# RFM69_20USB_20Gateway.net
KiCad netlist of a schematic drawn in EAGLE
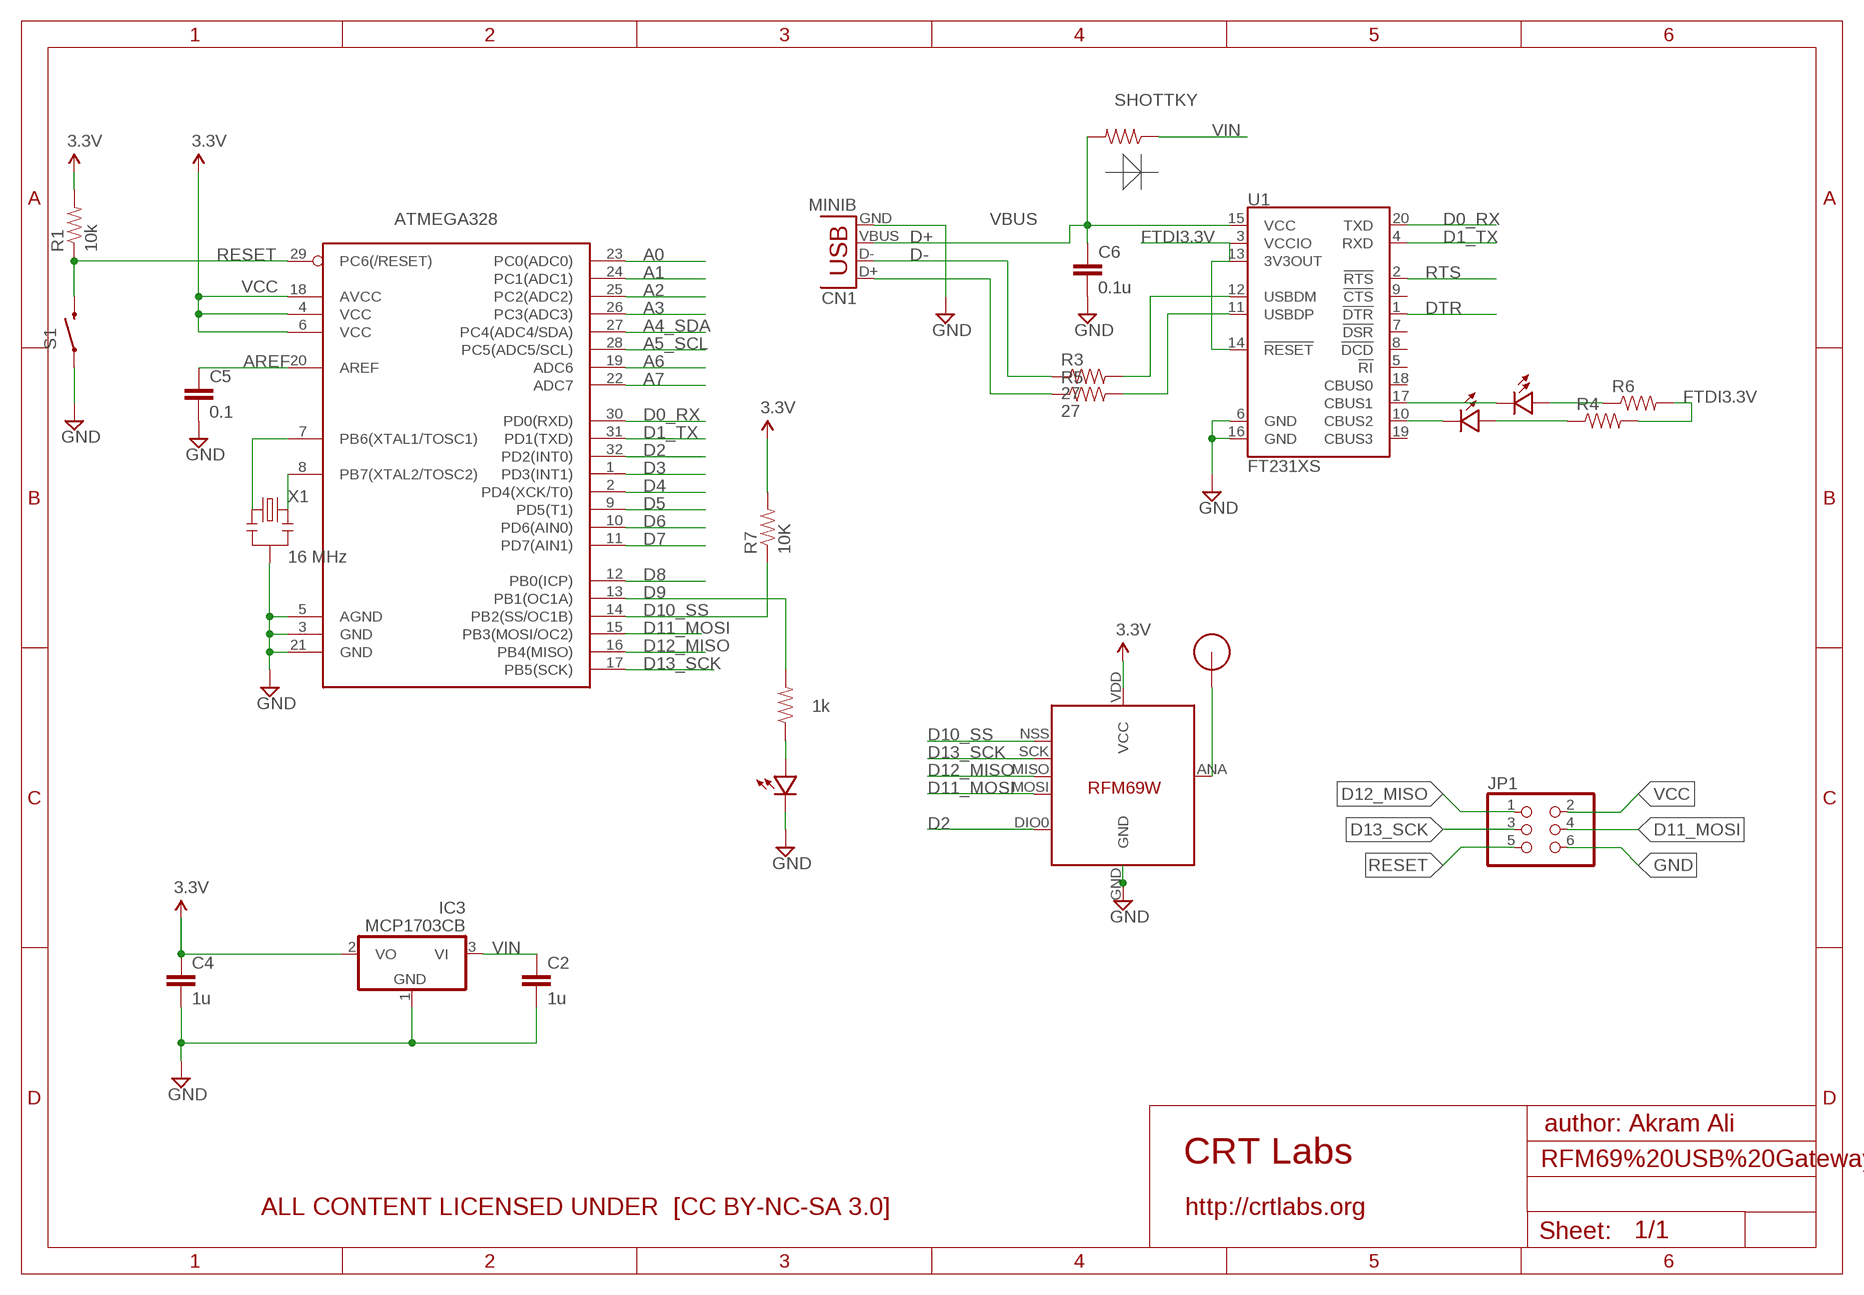
[diagram p0: schematic, sheet 1]

(export (version "E")
  (design (tool "Eeschema 10.0.6"))
  (components
    (comp (ref "ATMEGA328")
      (value "ATMega-328")
      (footprint "eagle-import:TQFP32-08")
      (libsource (lib "eagle-import") (part "ATMEGA168/328TQFP32"))
    )
    (comp (ref "C2")
      (value "1u")
      (footprint "eagle-import:0805")
      (libsource (lib "eagle-import") (part "SparkFun_CAP0805"))
    )
    (comp (ref "C4")
      (value "1u")
      (footprint "eagle-import:0805")
      (libsource (lib "eagle-import") (part "CAP0805"))
    )
    (comp (ref "C5")
      (value "0.1")
      (footprint "eagle-import:0805")
      (libsource (lib "eagle-import") (part "SparkFun_CAP0805"))
    )
    (comp (ref "C6")
      (value "0.1u")
      (footprint "eagle-import:0805")
      (libsource (lib "eagle-import") (part "SparkFun_CAP0805"))
    )
    (comp (ref "CN1")
      (value "MINIB")
      (footprint "eagle-import:USB-A-H")
      (libsource (lib "eagle-import") (part "USB-A-H"))
    )
    (comp (ref "D")
      (value "SHOTTKY")
      (footprint "eagle-import:0805")
      (libsource (lib "eagle-import") (part "RESISTOR0805"))
    )
    (comp (ref "IC3")
      (value "MCP1703CB")
      (footprint "eagle-import:SOT23")
      (libsource (lib "eagle-import") (part "MCP1703CB"))
    )
    (comp (ref "JP1")
      (value "PINHD-2X3")
      (footprint "eagle-import:2X03")
      (libsource (lib "eagle-import") (part "PINHD-2X3"))
    )
    (comp (ref "R1")
      (value "10k")
      (footprint "eagle-import:0805")
      (libsource (lib "eagle-import") (part "RESISTOR0805"))
    )
    (comp (ref "R2")
      (value "1k")
      (footprint "eagle-import:0805")
      (libsource (lib "eagle-import") (part "SparkFun_RESISTOR0805-RES"))
    )
    (comp (ref "R3")
      (value "27")
      (footprint "eagle-import:0805")
      (libsource (lib "eagle-import") (part "SparkFun_RESISTOR0805-RES"))
    )
    (comp (ref "R4")
      (value "RESISTOR0805-RES")
      (footprint "eagle-import:0805")
      (libsource (lib "eagle-import") (part "SparkFun_RESISTOR0805-RES"))
    )
    (comp (ref "R5")
      (value "27")
      (footprint "eagle-import:0805")
      (libsource (lib "eagle-import") (part "SparkFun_RESISTOR0805-RES"))
    )
    (comp (ref "R6")
      (value "RESISTOR0805-RES")
      (footprint "eagle-import:0805")
      (libsource (lib "eagle-import") (part "SparkFun_RESISTOR0805-RES"))
    )
    (comp (ref "R7")
      (value "10K")
      (footprint "eagle-import:0805")
      (libsource (lib "eagle-import") (part "SparkFun_RESISTOR0805-RES"))
    )
    (comp (ref "S1")
      (value "SWITCH-MOMENTARY-2SMD-ALT01")
      (footprint "eagle-import:TACTILE-SWITCH-SMD-ALT01")
      (libsource (lib "eagle-import") (part "SWITCH-MOMENTARY-2SMD-ALT01"))
    )
    (comp (ref "U$1")
      (value "RFM12B_ANTENNA")
      (footprint "eagle-import:RFM12B-ANTENNA")
      (libsource (lib "eagle-import") (part "RFM12B_ANTENNA"))
    )
    (comp (ref "U$2")
      (value "LED0805")
      (footprint "eagle-import:0805-LED")
      (libsource (lib "eagle-import") (part "LED0805"))
    )
    (comp (ref "U$4")
      (value "LED0805")
      (footprint "eagle-import:0805-LED")
      (libsource (lib "eagle-import") (part "LED0805"))
    )
    (comp (ref "U$5")
      (value "RFM69")
      (footprint "eagle-import:RFM69W-MINPADS")
      (libsource (lib "eagle-import") (part "RFM69"))
    )
    (comp (ref "U$7")
      (value "LED0805")
      (footprint "eagle-import:0805-LED")
      (libsource (lib "eagle-import") (part "LED0805"))
    )
    (comp (ref "U1")
      (value "FT231XS")
      (footprint "eagle-import:SSOP20_L")
      (libsource (lib "eagle-import") (part "FT231XS"))
    )
    (comp (ref "X1")
      (value "16 MHz")
      (footprint "eagle-import:RESONATOR-SMD")
      (libsource (lib "eagle-import") (part "RESONATORSMD"))
    )
  )
  (nets
    (net (code "1") (name "/A0") (class "Default")
      (node (ref "ATMEGA328") (pin "23") (pinfunction "PC0(ADC0)_23") (pintype "bidirectional"))
    )
    (net (code "2") (name "/A1") (class "Default")
      (node (ref "ATMEGA328") (pin "24") (pinfunction "PC1(ADC1)_24") (pintype "bidirectional"))
    )
    (net (code "3") (name "/A2") (class "Default")
      (node (ref "ATMEGA328") (pin "25") (pinfunction "PC2(ADC2)_25") (pintype "bidirectional"))
    )
    (net (code "4") (name "/A3") (class "Default")
      (node (ref "ATMEGA328") (pin "26") (pinfunction "PC3(ADC3)_26") (pintype "bidirectional"))
    )
    (net (code "5") (name "/A4_SDA") (class "Default")
      (node (ref "ATMEGA328") (pin "27") (pinfunction "PC4(ADC4/SDA)_27") (pintype "bidirectional"))
    )
    (net (code "6") (name "/A5_SCL") (class "Default")
      (node (ref "ATMEGA328") (pin "28") (pinfunction "PC5(ADC5/SCL)_28") (pintype "bidirectional"))
    )
    (net (code "7") (name "/A6") (class "Default")
      (node (ref "ATMEGA328") (pin "19") (pinfunction "ADC6_19") (pintype "bidirectional"))
    )
    (net (code "8") (name "/A7") (class "Default")
      (node (ref "ATMEGA328") (pin "22") (pinfunction "ADC7_22") (pintype "bidirectional"))
    )
    (net (code "9") (name "/AREF") (class "Default")
      (node (ref "ATMEGA328") (pin "20") (pinfunction "AREF_20") (pintype "bidirectional"))
      (node (ref "C5") (pin "1") (pinfunction "1_1") (pintype "passive"))
    )
    (net (code "10") (name "/D+") (class "Default")
      (node (ref "CN1") (pin "D+") (pinfunction "D+_D+") (pintype "bidirectional"))
      (node (ref "R5") (pin "1") (pinfunction "1_1") (pintype "passive"))
    )
    (net (code "11") (name "/D-") (class "Default")
      (node (ref "CN1") (pin "D-") (pinfunction "D-_D-") (pintype "bidirectional"))
      (node (ref "R3") (pin "1") (pinfunction "1_1") (pintype "passive"))
    )
    (net (code "12") (name "/D0_RX") (class "Default")
      (node (ref "ATMEGA328") (pin "30") (pinfunction "PD0(RXD)_30") (pintype "bidirectional"))
      (node (ref "U1") (pin "20") (pinfunction "TXD_20") (pintype "bidirectional"))
    )
    (net (code "13") (name "/D1_TX") (class "Default")
      (node (ref "ATMEGA328") (pin "31") (pinfunction "PD1(TXD)_31") (pintype "bidirectional"))
      (node (ref "U1") (pin "4") (pinfunction "RXD_4") (pintype "bidirectional"))
    )
    (net (code "14") (name "/D2") (class "Default")
      (node (ref "ATMEGA328") (pin "32") (pinfunction "PD2(INT0)_32") (pintype "bidirectional"))
      (node (ref "U$5") (pin "DIO0") (pinfunction "DIO0_DIO0") (pintype "open_collector"))
    )
    (net (code "15") (name "/D3") (class "Default")
      (node (ref "ATMEGA328") (pin "1") (pinfunction "PD3(INT1)_1") (pintype "bidirectional"))
    )
    (net (code "16") (name "/D4") (class "Default")
      (node (ref "ATMEGA328") (pin "2") (pinfunction "PD4(XCK/T0)_2") (pintype "bidirectional"))
    )
    (net (code "17") (name "/D5") (class "Default")
      (node (ref "ATMEGA328") (pin "9") (pinfunction "PD5(T1)_9") (pintype "bidirectional"))
    )
    (net (code "18") (name "/D6") (class "Default")
      (node (ref "ATMEGA328") (pin "10") (pinfunction "PD6(AIN0)_10") (pintype "bidirectional"))
    )
    (net (code "19") (name "/D7") (class "Default")
      (node (ref "ATMEGA328") (pin "11") (pinfunction "PD7(AIN1)_11") (pintype "bidirectional"))
    )
    (net (code "20") (name "/D8") (class "Default")
      (node (ref "ATMEGA328") (pin "12") (pinfunction "PB0(ICP)_12") (pintype "bidirectional"))
    )
    (net (code "21") (name "/D9") (class "Default")
      (node (ref "ATMEGA328") (pin "13") (pinfunction "PB1(OC1A)_13") (pintype "bidirectional"))
      (node (ref "R2") (pin "2") (pinfunction "2_2") (pintype "passive"))
    )
    (net (code "22") (name "/D10_SS") (class "Default")
      (node (ref "ATMEGA328") (pin "14") (pinfunction "PB2(SS/OC1B)_14") (pintype "bidirectional"))
      (node (ref "R7") (pin "1") (pinfunction "1_1") (pintype "passive"))
      (node (ref "U$5") (pin "NSS") (pinfunction "SEL_NSS") (pintype "input"))
    )
    (net (code "23") (name "/DTR") (class "Default")
      (node (ref "U1") (pin "1") (pinfunction "~{DTR}_1") (pintype "bidirectional"))
    )
    (net (code "24") (name "/FTDI3.3V") (class "Default")
      (node (ref "R4") (pin "2") (pinfunction "2_2") (pintype "passive"))
      (node (ref "R6") (pin "2") (pinfunction "2_2") (pintype "passive"))
      (node (ref "U1") (pin "13") (pinfunction "3V3OUT_13") (pintype "bidirectional"))
      (node (ref "U1") (pin "14") (pinfunction "~{RESET}_14") (pintype "bidirectional"))
      (node (ref "U1") (pin "3") (pinfunction "VCCIO_3") (pintype "bidirectional"))
    )
    (net (code "25") (name "/RTS") (class "Default")
      (node (ref "U1") (pin "2") (pinfunction "~{RTS}_2") (pintype "bidirectional"))
    )
    (net (code "26") (name "/VBUS") (class "Default")
      (node (ref "C6") (pin "1") (pinfunction "1_1") (pintype "passive"))
      (node (ref "CN1") (pin "VBUS") (pinfunction "VBUS_VBUS") (pintype "bidirectional"))
      (node (ref "D") (pin "2") (pinfunction "2_2") (pintype "passive"))
      (node (ref "U1") (pin "15") (pinfunction "VCC_15") (pintype "bidirectional"))
    )
    (net (code "27") (name "/VIN") (class "Default")
      (node (ref "C2") (pin "1") (pinfunction "1_1") (pintype "passive"))
      (node (ref "D") (pin "1") (pinfunction "1_1") (pintype "passive"))
      (node (ref "IC3") (pin "3") (pinfunction "VI_3") (pintype "input"))
    )
    (net (code "28") (name "D11_MOSI") (class "Default")
      (node (ref "ATMEGA328") (pin "15") (pinfunction "PB3(MOSI/OC2)_15") (pintype "bidirectional"))
      (node (ref "JP1") (pin "4") (pinfunction "4_4") (pintype "passive"))
      (node (ref "U$5") (pin "MOSI") (pinfunction "MOSI_MOSI") (pintype "output"))
    )
    (net (code "29") (name "D12_MISO") (class "Default")
      (node (ref "ATMEGA328") (pin "16") (pinfunction "PB4(MISO)_16") (pintype "bidirectional"))
      (node (ref "JP1") (pin "1") (pinfunction "1_1") (pintype "passive"))
      (node (ref "U$5") (pin "MISO") (pinfunction "MISO_MISO") (pintype "input"))
    )
    (net (code "30") (name "D13_SCK") (class "Default")
      (node (ref "ATMEGA328") (pin "17") (pinfunction "PB5(SCK)_17") (pintype "bidirectional"))
      (node (ref "JP1") (pin "3") (pinfunction "3_3") (pintype "passive"))
      (node (ref "U$5") (pin "SCK") (pinfunction "SCK_SCK") (pintype "input"))
    )
    (net (code "31") (name "GND") (class "Default")
      (node (ref "ATMEGA328") (pin "21") (pinfunction "GND_21") (pintype "bidirectional"))
      (node (ref "ATMEGA328") (pin "3") (pinfunction "GND_3") (pintype "bidirectional"))
      (node (ref "ATMEGA328") (pin "5") (pinfunction "AGND_5") (pintype "bidirectional"))
      (node (ref "C2") (pin "2") (pinfunction "2_2") (pintype "passive"))
      (node (ref "C4") (pin "2") (pinfunction "2_2") (pintype "passive"))
      (node (ref "C5") (pin "2") (pinfunction "2_2") (pintype "passive"))
      (node (ref "C6") (pin "2") (pinfunction "2_2") (pintype "passive"))
      (node (ref "CN1") (pin "GND") (pinfunction "GND_GND") (pintype "bidirectional"))
      (node (ref "IC3") (pin "1") (pinfunction "GND_1") (pintype "passive"))
      (node (ref "JP1") (pin "6") (pinfunction "6_6") (pintype "passive"))
      (node (ref "S1") (pin "1") (pinfunction "1_1") (pintype "passive"))
      (node (ref "S1") (pin "2") (pinfunction "1_2") (pintype "passive"))
      (node (ref "U$2") (pin "MINUS") (pinfunction "MINUS_MINUS") (pintype "passive"))
      (node (ref "U$5") (pin "GND") (pinfunction "GND_GND") (pintype "power_in"))
      (node (ref "U1") (pin "16") (pinfunction "GND_16") (pintype "bidirectional"))
      (node (ref "U1") (pin "6") (pinfunction "GND_6") (pintype "bidirectional"))
      (node (ref "X1") (pin "2") (pinfunction "2_2") (pintype "passive"))
    )
    (net (code "32") (name "Net-(ATMEGA328-PB6(XTAL1{slash}TOSC1))") (class "Default")
      (node (ref "ATMEGA328") (pin "7") (pinfunction "PB6(XTAL1/TOSC1)_7") (pintype "bidirectional"))
      (node (ref "X1") (pin "1") (pinfunction "1_1") (pintype "passive"))
    )
    (net (code "33") (name "Net-(ATMEGA328-PB7(XTAL2{slash}TOSC2))") (class "Default")
      (node (ref "ATMEGA328") (pin "8") (pinfunction "PB7(XTAL2/TOSC2)_8") (pintype "bidirectional"))
      (node (ref "X1") (pin "3") (pinfunction "3_3") (pintype "passive"))
    )
    (net (code "34") (name "Net-(R2-Pad1)") (class "Default")
      (node (ref "R2") (pin "1") (pinfunction "1_1") (pintype "passive"))
      (node (ref "U$2") (pin "PLUS") (pinfunction "PLUS_PLUS") (pintype "passive"))
    )
    (net (code "35") (name "Net-(R4-Pad1)") (class "Default")
      (node (ref "R4") (pin "1") (pinfunction "1_1") (pintype "passive"))
      (node (ref "U$7") (pin "PLUS") (pinfunction "PLUS_PLUS") (pintype "passive"))
    )
    (net (code "36") (name "Net-(R6-Pad1)") (class "Default")
      (node (ref "R6") (pin "1") (pinfunction "1_1") (pintype "passive"))
      (node (ref "U$4") (pin "PLUS") (pinfunction "PLUS_PLUS") (pintype "passive"))
    )
    (net (code "37") (name "Net-(U$1-1)") (class "Default")
      (node (ref "U$1") (pin "P$1") (pinfunction "1_P$1") (pintype "bidirectional"))
      (node (ref "U$5") (pin "ANA") (pinfunction "ANT_ANA") (pintype "passive"))
    )
    (net (code "38") (name "Net-(U1-CBUS1)") (class "Default")
      (node (ref "U$4") (pin "MINUS") (pinfunction "MINUS_MINUS") (pintype "passive"))
      (node (ref "U1") (pin "17") (pinfunction "CBUS1_17") (pintype "bidirectional"))
    )
    (net (code "39") (name "Net-(U1-CBUS2)") (class "Default")
      (node (ref "U$7") (pin "MINUS") (pinfunction "MINUS_MINUS") (pintype "passive"))
      (node (ref "U1") (pin "10") (pinfunction "CBUS2_10") (pintype "bidirectional"))
    )
    (net (code "40") (name "Net-(U1-USBDM)") (class "Default")
      (node (ref "R3") (pin "2") (pinfunction "2_2") (pintype "passive"))
      (node (ref "U1") (pin "12") (pinfunction "USBDM_12") (pintype "bidirectional"))
    )
    (net (code "41") (name "Net-(U1-USBDP)") (class "Default")
      (node (ref "R5") (pin "2") (pinfunction "2_2") (pintype "passive"))
      (node (ref "U1") (pin "11") (pinfunction "USBDP_11") (pintype "bidirectional"))
    )
    (net (code "42") (name "RESET") (class "Default")
      (node (ref "ATMEGA328") (pin "29") (pinfunction "PC6(/RESET)_29") (pintype "bidirectional"))
      (node (ref "JP1") (pin "5") (pinfunction "5_5") (pintype "passive"))
      (node (ref "R1") (pin "1") (pinfunction "1_1") (pintype "passive"))
      (node (ref "S1") (pin "3") (pinfunction "2_3") (pintype "passive"))
      (node (ref "S1") (pin "4") (pinfunction "2_4") (pintype "passive"))
    )
    (net (code "43") (name "VCC") (class "Default")
      (node (ref "ATMEGA328") (pin "18") (pinfunction "AVCC_18") (pintype "bidirectional"))
      (node (ref "ATMEGA328") (pin "4") (pinfunction "VCC_4") (pintype "bidirectional"))
      (node (ref "ATMEGA328") (pin "6") (pinfunction "VCC_6") (pintype "bidirectional"))
      (node (ref "C4") (pin "1") (pinfunction "1_1") (pintype "passive"))
      (node (ref "IC3") (pin "2") (pinfunction "VO_2") (pintype "passive"))
      (node (ref "JP1") (pin "2") (pinfunction "2_2") (pintype "passive"))
      (node (ref "R1") (pin "2") (pinfunction "2_2") (pintype "passive"))
      (node (ref "R7") (pin "2") (pinfunction "2_2") (pintype "passive"))
      (node (ref "U$5") (pin "VDD") (pinfunction "VCC_VDD") (pintype "power_in"))
    )
    (net (code "44") (name "unconnected-(U1-CBUS0-Pad18)") (class "Default")
      (node (ref "U1") (pin "18") (pinfunction "CBUS0_18") (pintype "bidirectional"))
    )
    (net (code "45") (name "unconnected-(U1-CBUS3-Pad19)") (class "Default")
      (node (ref "U1") (pin "19") (pinfunction "CBUS3_19") (pintype "bidirectional"))
    )
    (net (code "46") (name "unconnected-(U1-~{CTS}-Pad9)") (class "Default")
      (node (ref "U1") (pin "9") (pinfunction "~{CTS}_9") (pintype "bidirectional"))
    )
    (net (code "47") (name "unconnected-(U1-~{DCD}-Pad8)") (class "Default")
      (node (ref "U1") (pin "8") (pinfunction "~{DCD}_8") (pintype "bidirectional"))
    )
    (net (code "48") (name "unconnected-(U1-~{DSR}-Pad7)") (class "Default")
      (node (ref "U1") (pin "7") (pinfunction "~{DSR}_7") (pintype "bidirectional"))
    )
    (net (code "49") (name "unconnected-(U1-~{RI}-Pad5)") (class "Default")
      (node (ref "U1") (pin "5") (pinfunction "~{RI}_5") (pintype "bidirectional"))
    )
  )
)
